# light_sensor_basic.net
KiCad netlist of a schematic drawn in EAGLE
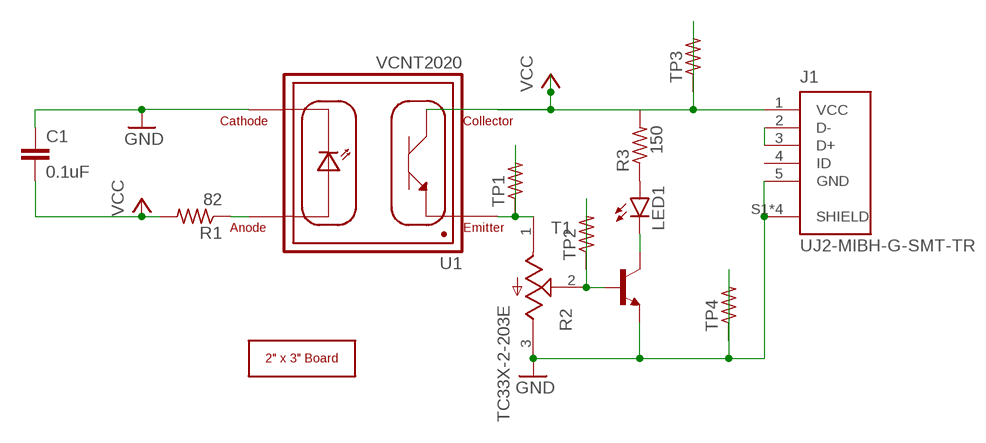
[diagram p0: schematic, sheet 1]

(export (version "E")
  (design (tool "Eeschema 10.0.6"))
  (components
    (comp (ref "C1")
      (value "0.1uF")
      (footprint "eagle-import:C1206")
      (libsource (lib "eagle-import") (part "C-EUC1206"))
    )
    (comp (ref "J1")
      (value "UJ2-MIBH-G-SMT-TR")
      (footprint "eagle-import:CUI_UJ2-MIBH-G-SMT-TR")
      (fields (field (name "MANUFACTURER") "CUI"))
      (libsource (lib "eagle-import") (part "UJ2-MIBH-G-SMT-TR"))
    )
    (comp (ref "LED1")
      (value "LEDSML0805")
      (footprint "eagle-import:SML0805")
      (libsource (lib "eagle-import") (part "LEDSML0805"))
    )
    (comp (ref "R1")
      (value "82")
      (footprint "eagle-import:R1206")
      (libsource (lib "eagle-import") (part "R-US_R1206"))
    )
    (comp (ref "R2")
      (value "TC33X-2-203E")
      (footprint "eagle-import:TRIM_TC33X-2-203E")
      (fields (field (name "DIGIKEY_PART_NUMBER") "TC33X-2-203ETR-ND") (field (name "MF") "Bourns"))
      (libsource (lib "eagle-import") (part "TC33X-2-203E"))
    )
    (comp (ref "R3")
      (value "150")
      (footprint "eagle-import:R0805")
      (libsource (lib "eagle-import") (part "R-US_R0805"))
    )
    (comp (ref "T1")
      (value "-NPN-SOT23-EBC")
      (footprint "eagle-import:SOT23-EBC")
      (libsource (lib "eagle-import") (part "-NPN-SOT23-EBC"))
    )
    (comp (ref "TP1")
      (value "R-US_R0805")
      (footprint "eagle-import:R0805")
      (libsource (lib "eagle-import") (part "R-US_R0805"))
    )
    (comp (ref "TP2")
      (value "R-US_R1206")
      (footprint "eagle-import:R1206")
      (libsource (lib "eagle-import") (part "R-US_R1206"))
    )
    (comp (ref "TP3")
      (value "R-US_R1206")
      (footprint "eagle-import:R1206")
      (libsource (lib "eagle-import") (part "R-US_R1206"))
    )
    (comp (ref "TP4")
      (value "R-US_R1206")
      (footprint "eagle-import:R1206")
      (libsource (lib "eagle-import") (part "R-US_R1206"))
    )
    (comp (ref "U$1")
      (value "2X3_BOARD_V2")
      (footprint "eagle-import:2X3_BOARD_V2")
      (libsource (lib "eagle-import") (part "2X3_BOARD_V2"))
    )
    (comp (ref "U1")
      (value "VCNT2020")
      (footprint "eagle-import:XDCR_VCNT2020")
      (fields (field (name "DIGIKEY_PART_NUMBER") "VCNT2020TR-ND") (field (name "MF") "Vishay"))
      (libsource (lib "eagle-import") (part "VCNT2020"))
    )
  )
  (nets
    (net (code "1") (name "GND") (class "Default")
      (node (ref "C1") (pin "1") (pinfunction "1_1") (pintype "passive"))
      (node (ref "J1") (pin "5") (pinfunction "GND_5") (pintype "power_in"))
      (node (ref "J1") (pin "S1") (pinfunction "SHIELD_S1") (pintype "passive"))
      (node (ref "J1") (pin "S2") (pinfunction "SHIELD_S2") (pintype "passive"))
      (node (ref "J1") (pin "S3") (pinfunction "SHIELD_S3") (pintype "passive"))
      (node (ref "J1") (pin "S4") (pinfunction "SHIELD_S4") (pintype "passive"))
      (node (ref "R2") (pin "3") (pinfunction "CW_3") (pintype "passive"))
      (node (ref "T1") (pin "E") (pinfunction "E_E") (pintype "passive"))
      (node (ref "TP4") (pin "1") (pinfunction "1_1") (pintype "passive"))
      (node (ref "TP4") (pin "2") (pinfunction "2_2") (pintype "passive"))
      (node (ref "U1") (pin "4") (pinfunction "CATHODE_4") (pintype "passive"))
    )
    (net (code "2") (name "Net-(J1-D+)") (class "Default")
      (node (ref "J1") (pin "2") (pinfunction "D-_2") (pintype "bidirectional"))
      (node (ref "J1") (pin "3") (pinfunction "D+_3") (pintype "bidirectional"))
    )
    (net (code "3") (name "Net-(LED1-PadA)") (class "Default")
      (node (ref "LED1") (pin "A") (pinfunction "A_A") (pintype "passive"))
      (node (ref "R3") (pin "1") (pinfunction "1_1") (pintype "passive"))
    )
    (net (code "4") (name "Net-(LED1-PadC)") (class "Default")
      (node (ref "LED1") (pin "C") (pinfunction "C_C") (pintype "passive"))
      (node (ref "T1") (pin "C") (pinfunction "C_C") (pintype "passive"))
    )
    (net (code "5") (name "Net-(R2-CCW)") (class "Default")
      (node (ref "R2") (pin "1") (pinfunction "CCW_1") (pintype "passive"))
      (node (ref "TP1") (pin "1") (pinfunction "1_1") (pintype "passive"))
      (node (ref "TP1") (pin "2") (pinfunction "2_2") (pintype "passive"))
      (node (ref "U1") (pin "1") (pinfunction "EMITTER_1") (pintype "passive"))
    )
    (net (code "6") (name "Net-(R2-W)") (class "Default")
      (node (ref "R2") (pin "2") (pinfunction "W_2") (pintype "passive"))
      (node (ref "T1") (pin "B") (pinfunction "B_B") (pintype "passive"))
      (node (ref "TP2") (pin "1") (pinfunction "1_1") (pintype "passive"))
      (node (ref "TP2") (pin "2") (pinfunction "2_2") (pintype "passive"))
    )
    (net (code "7") (name "Net-(U1-ANODE)") (class "Default")
      (node (ref "R1") (pin "1") (pinfunction "1_1") (pintype "passive"))
      (node (ref "U1") (pin "3") (pinfunction "ANODE_3") (pintype "passive"))
    )
    (net (code "8") (name "VCC") (class "Default")
      (node (ref "C1") (pin "2") (pinfunction "2_2") (pintype "passive"))
      (node (ref "J1") (pin "1") (pinfunction "VCC_1") (pintype "power_in"))
      (node (ref "R1") (pin "2") (pinfunction "2_2") (pintype "passive"))
      (node (ref "R3") (pin "2") (pinfunction "2_2") (pintype "passive"))
      (node (ref "TP3") (pin "1") (pinfunction "1_1") (pintype "passive"))
      (node (ref "TP3") (pin "2") (pinfunction "2_2") (pintype "passive"))
      (node (ref "U1") (pin "2") (pinfunction "COLLECTOR_2") (pintype "passive"))
    )
    (net (code "9") (name "unconnected-(J1-ID-Pad4)") (class "Default")
      (node (ref "J1") (pin "4") (pinfunction "ID_4") (pintype "bidirectional"))
    )
  )
)
